# zgrzewarka3_-_do_szko_y.net
KiCad netlist of a schematic drawn in EAGLE
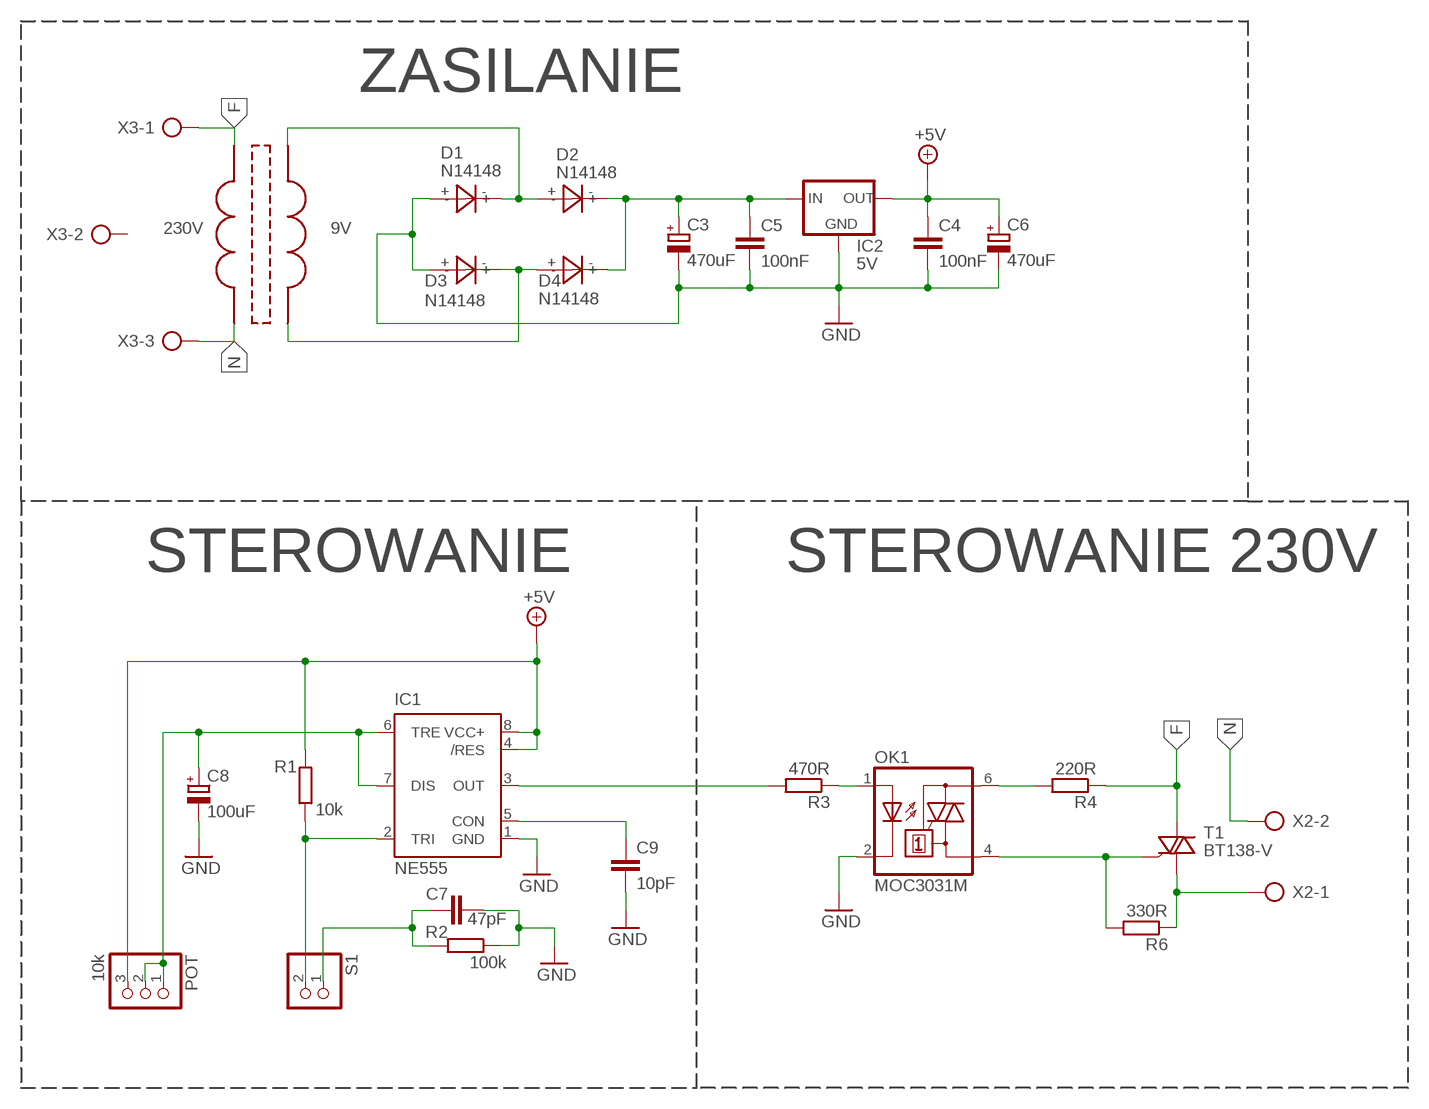
[diagram p0: schematic, sheet 1]

(export (version "E")
  (design (tool "Eeschema 10.0.6"))
  (components
    (comp (ref "C3")
      (value "470uF")
      (footprint "eagle-import:C5-8,5")
      (libsource (lib "eagle-import") (part "C-EU-POL'''"))
    )
    (comp (ref "C4")
      (value "100nF")
      (footprint "eagle-import:C50-45-75")
      (libsource (lib "eagle-import") (part "C-EU050-045-075"))
    )
    (comp (ref "C5")
      (value "100nF")
      (footprint "eagle-import:C50-45-75")
      (libsource (lib "eagle-import") (part "C-EU050-045-075"))
    )
    (comp (ref "C6")
      (value "470uF")
      (footprint "eagle-import:C5-8,5")
      (libsource (lib "eagle-import") (part "C-EU-POL'''"))
    )
    (comp (ref "C7")
      (value "47pF")
      (footprint "eagle-import:C50-45-75")
      (libsource (lib "eagle-import") (part "C-EU050-045-075"))
    )
    (comp (ref "C8")
      (value "100uF")
      (footprint "eagle-import:C5-8,5")
      (libsource (lib "eagle-import") (part "C-EU-POL'''"))
    )
    (comp (ref "C9")
      (value "10pF")
      (footprint "eagle-import:C50-45-75")
      (libsource (lib "eagle-import") (part "C-EU050-045-075"))
    )
    (comp (ref "D1")
      (value "N14148")
      (footprint "eagle-import:DO35-7")
      (libsource (lib "eagle-import") (part "N14148"))
    )
    (comp (ref "D2")
      (value "N14148")
      (footprint "eagle-import:DO35-7")
      (libsource (lib "eagle-import") (part "N14148"))
    )
    (comp (ref "D3")
      (value "N14148")
      (footprint "eagle-import:DO35-7")
      (libsource (lib "eagle-import") (part "N14148"))
    )
    (comp (ref "D4")
      (value "N14148")
      (footprint "eagle-import:DO35-7")
      (libsource (lib "eagle-import") (part "N14148"))
    )
    (comp (ref "IC1")
      (value "NE555")
      (footprint "eagle-import:DIL-08")
      (fields (field (name "MF") "Arrow Electronics") (field (name "MPN") "NE555N"))
      (libsource (lib "eagle-import") (part "NE555"))
    )
    (comp (ref "IC2")
      (value "5V")
      (footprint "eagle-import:78LXX")
      (libsource (lib "eagle-import") (part "78LXX"))
    )
    (comp (ref "OK1")
      (value "MOC3031M")
      (footprint "eagle-import:DIL06")
      (fields (field (name "MF") "FAIRCHILD SEMICONDUCTOR"))
      (libsource (lib "eagle-import") (part "MOC3031M"))
    )
    (comp (ref "POT")
      (value "10k")
      (footprint "eagle-import:1X03")
      (libsource (lib "eagle-import") (part "PINHD-1X3"))
    )
    (comp (ref "R1")
      (value "10k")
      (footprint "eagle-import:204_7")
      (libsource (lib "eagle-import") (part "R-EU7"))
    )
    (comp (ref "R2")
      (value "100k")
      (footprint "eagle-import:204_7")
      (libsource (lib "eagle-import") (part "R-EU7"))
    )
    (comp (ref "R3")
      (value "470R")
      (footprint "eagle-import:204_7")
      (libsource (lib "eagle-import") (part "R-EU7"))
    )
    (comp (ref "R4")
      (value "220R")
      (footprint "eagle-import:204_7")
      (libsource (lib "eagle-import") (part "R-EU7"))
    )
    (comp (ref "R6")
      (value "330R")
      (footprint "eagle-import:204_7")
      (libsource (lib "eagle-import") (part "R-EU7"))
    )
    (comp (ref "S1")
      (value "PINHD-1X2")
      (footprint "eagle-import:1X02")
      (libsource (lib "eagle-import") (part "PINHD-1X2"))
    )
    (comp (ref "T1")
      (value "BT138-V")
      (footprint "eagle-import:TO220BV")
      (libsource (lib "eagle-import") (part "BT138-V"))
    )
    (comp (ref "U$1")
      (value "TRAFO-9V")
      (footprint "eagle-import:OBUDOWA1")
      (libsource (lib "eagle-import") (part "TRAFO-9V"))
    )
    (comp (ref "X2")
      (value "AK300/2")
      (footprint "eagle-import:AK300_2")
      (libsource (lib "eagle-import") (part "AK300/2"))
    )
    (comp (ref "X3")
      (value "AK300/3")
      (footprint "eagle-import:AK300_3")
      (libsource (lib "eagle-import") (part "AK300/3"))
    )
  )
  (nets
    (net (code "1") (name "+5V") (class "Default")
      (node (ref "C4") (pin "P$1") (pinfunction "1_P$1") (pintype "passive"))
      (node (ref "C6") (pin "+") (pinfunction "+_+") (pintype "passive"))
      (node (ref "IC1") (pin "4") (pinfunction "/RES_4") (pintype "input"))
      (node (ref "IC1") (pin "8") (pinfunction "VCC+_8") (pintype "power_in"))
      (node (ref "IC2") (pin "OUT") (pinfunction "OUT_OUT") (pintype "passive"))
      (node (ref "POT") (pin "3") (pinfunction "3_3") (pintype "passive"))
      (node (ref "R1") (pin "P$2") (pinfunction "2_P$2") (pintype "passive"))
    )
    (net (code "2") (name "F") (class "Default")
      (node (ref "R4") (pin "P$1") (pinfunction "1_P$1") (pintype "passive"))
      (node (ref "T1") (pin "T2") (pinfunction "A2_T2") (pintype "passive"))
      (node (ref "U$1") (pin "230V-1") (pinfunction "230V-1_230V-1") (pintype "bidirectional"))
      (node (ref "X3") (pin "1") (pinfunction "KL_1") (pintype "passive"))
    )
    (net (code "3") (name "GND") (class "Default")
      (node (ref "C3") (pin "-") (pinfunction "-_-") (pintype "passive"))
      (node (ref "C4") (pin "P$2") (pinfunction "2_P$2") (pintype "passive"))
      (node (ref "C5") (pin "P$2") (pinfunction "2_P$2") (pintype "passive"))
      (node (ref "C6") (pin "-") (pinfunction "-_-") (pintype "passive"))
      (node (ref "C7") (pin "P$2") (pinfunction "2_P$2") (pintype "passive"))
      (node (ref "C8") (pin "-") (pinfunction "-_-") (pintype "passive"))
      (node (ref "C9") (pin "P$2") (pinfunction "2_P$2") (pintype "passive"))
      (node (ref "D1") (pin "+") (pinfunction "+_+") (pintype "bidirectional"))
      (node (ref "D3") (pin "+") (pinfunction "+_+") (pintype "bidirectional"))
      (node (ref "IC1") (pin "1") (pinfunction "GND_1") (pintype "power_in"))
      (node (ref "IC2") (pin "GND") (pinfunction "GND_GND") (pintype "input"))
      (node (ref "OK1") (pin "2") (pinfunction "C_2") (pintype "passive"))
      (node (ref "R2") (pin "P$1") (pinfunction "1_P$1") (pintype "passive"))
    )
    (net (code "4") (name "N") (class "Default")
      (node (ref "U$1") (pin "230V-2") (pinfunction "230V-2_230V-2") (pintype "bidirectional"))
      (node (ref "X2") (pin "2") (pinfunction "KL_2") (pintype "passive"))
      (node (ref "X3") (pin "3") (pinfunction "KL_3") (pintype "passive"))
    )
    (net (code "5") (name "Net-(C5-1)") (class "Default")
      (node (ref "C3") (pin "+") (pinfunction "+_+") (pintype "passive"))
      (node (ref "C5") (pin "P$1") (pinfunction "1_P$1") (pintype "passive"))
      (node (ref "D2") (pin "-") (pinfunction "-_-") (pintype "bidirectional"))
      (node (ref "D4") (pin "-") (pinfunction "-_-") (pintype "bidirectional"))
      (node (ref "IC2") (pin "IN") (pinfunction "IN_IN") (pintype "input"))
    )
    (net (code "6") (name "Net-(C7-1)") (class "Default")
      (node (ref "C7") (pin "P$1") (pinfunction "1_P$1") (pintype "passive"))
      (node (ref "R2") (pin "P$2") (pinfunction "2_P$2") (pintype "passive"))
      (node (ref "S1") (pin "1") (pinfunction "1_1") (pintype "passive"))
    )
    (net (code "7") (name "Net-(C9-1)") (class "Default")
      (node (ref "C9") (pin "P$1") (pinfunction "1_P$1") (pintype "passive"))
      (node (ref "IC1") (pin "5") (pinfunction "CON_5") (pintype "input"))
    )
    (net (code "8") (name "Net-(D1-Pad-)") (class "Default")
      (node (ref "D1") (pin "-") (pinfunction "-_-") (pintype "bidirectional"))
      (node (ref "D2") (pin "+") (pinfunction "+_+") (pintype "bidirectional"))
      (node (ref "U$1") (pin "9V-1") (pinfunction "9V-1_9V-1") (pintype "bidirectional"))
    )
    (net (code "9") (name "Net-(D3-Pad-)") (class "Default")
      (node (ref "D3") (pin "-") (pinfunction "-_-") (pintype "bidirectional"))
      (node (ref "D4") (pin "+") (pinfunction "+_+") (pintype "bidirectional"))
      (node (ref "U$1") (pin "9V-2") (pinfunction "9V-2_9V-2") (pintype "bidirectional"))
    )
    (net (code "10") (name "Net-(IC1-DIS)") (class "Default")
      (node (ref "C8") (pin "+") (pinfunction "+_+") (pintype "passive"))
      (node (ref "IC1") (pin "6") (pinfunction "TRE_6") (pintype "input"))
      (node (ref "IC1") (pin "7") (pinfunction "DIS_7") (pintype "input"))
      (node (ref "POT") (pin "1") (pinfunction "1_1") (pintype "passive"))
      (node (ref "POT") (pin "2") (pinfunction "2_2") (pintype "passive"))
    )
    (net (code "11") (name "Net-(IC1-OUT)") (class "Default")
      (node (ref "IC1") (pin "3") (pinfunction "OUT_3") (pintype "output"))
      (node (ref "R3") (pin "P$2") (pinfunction "2_P$2") (pintype "passive"))
    )
    (net (code "12") (name "Net-(IC1-TRI)") (class "Default")
      (node (ref "IC1") (pin "2") (pinfunction "TRI_2") (pintype "input"))
      (node (ref "R1") (pin "P$1") (pinfunction "1_P$1") (pintype "passive"))
      (node (ref "S1") (pin "2") (pinfunction "2_2") (pintype "passive"))
    )
    (net (code "13") (name "Net-(OK1-A)") (class "Default")
      (node (ref "OK1") (pin "1") (pinfunction "A_1") (pintype "passive"))
      (node (ref "R3") (pin "P$1") (pinfunction "1_P$1") (pintype "passive"))
    )
    (net (code "14") (name "Net-(OK1-A1)") (class "Default")
      (node (ref "OK1") (pin "4") (pinfunction "A1_4") (pintype "passive"))
      (node (ref "R6") (pin "P$2") (pinfunction "2_P$2") (pintype "passive"))
      (node (ref "T1") (pin "G") (pinfunction "G_G") (pintype "passive"))
    )
    (net (code "15") (name "Net-(OK1-A2)") (class "Default")
      (node (ref "OK1") (pin "6") (pinfunction "A2_6") (pintype "passive"))
      (node (ref "R4") (pin "P$2") (pinfunction "2_P$2") (pintype "passive"))
    )
    (net (code "16") (name "Net-(R6-1)") (class "Default")
      (node (ref "R6") (pin "P$1") (pinfunction "1_P$1") (pintype "passive"))
      (node (ref "T1") (pin "T1") (pinfunction "A1_T1") (pintype "passive"))
      (node (ref "X2") (pin "1") (pinfunction "KL_1") (pintype "passive"))
    )
    (net (code "17") (name "unconnected-(X3B-KL-Pad2)") (class "Default")
      (node (ref "X3") (pin "2") (pinfunction "KL_2") (pintype "passive"))
    )
  )
)
